# Heartrate_Monitor_External.net
KiCad netlist of a schematic drawn in Altium Designer
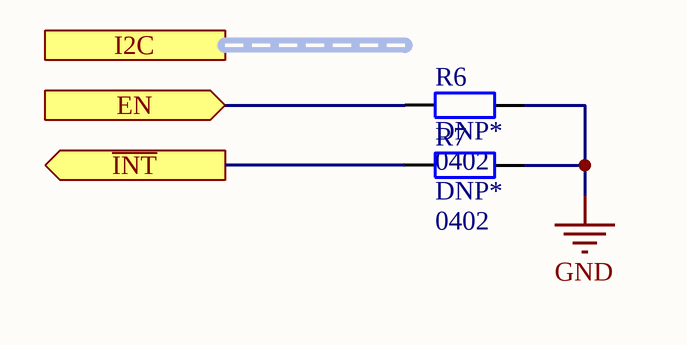
[diagram p0: Heartrate_Monitor_External.SchDoc]

(export (version "E")
  (design (tool "Eeschema 10.0.6"))
  (components
    (comp (ref "R6")
      (value "DNP*")
      (footprint "0402R")
      (description "Placeholder for a 0402 resistor")
      (fields (field (name "CASE/PACKAGE") "0402"))
      (libsource (lib "resistors_smd") (part "RES SMD NO BOM 0402"))
    )
    (comp (ref "R7")
      (value "DNP*")
      (footprint "0402R")
      (description "Placeholder for a 0402 resistor")
      (fields (field (name "CASE/PACKAGE") "0402"))
      (libsource (lib "resistors_smd") (part "RES SMD NO BOM 0402"))
    )
  )
  (nets
    (net (code "2") (name "/EN") (class "Default")
      (node (ref "R6") (pin "2") (pinfunction "2_2") (pintype "passive"))
    )
    (net (code "4") (name "/INT") (class "Default")
      (node (ref "R7") (pin "2") (pinfunction "2_2") (pintype "passive"))
    )
    (net (code "5") (name "GND") (class "Default")
      (node (ref "R6") (pin "1") (pinfunction "1_1") (pintype "passive"))
      (node (ref "R7") (pin "1") (pinfunction "1_1") (pintype "passive"))
    )
  )
)
